# XFader_Assign.net
KiCad netlist of a schematic drawn in EAGLE
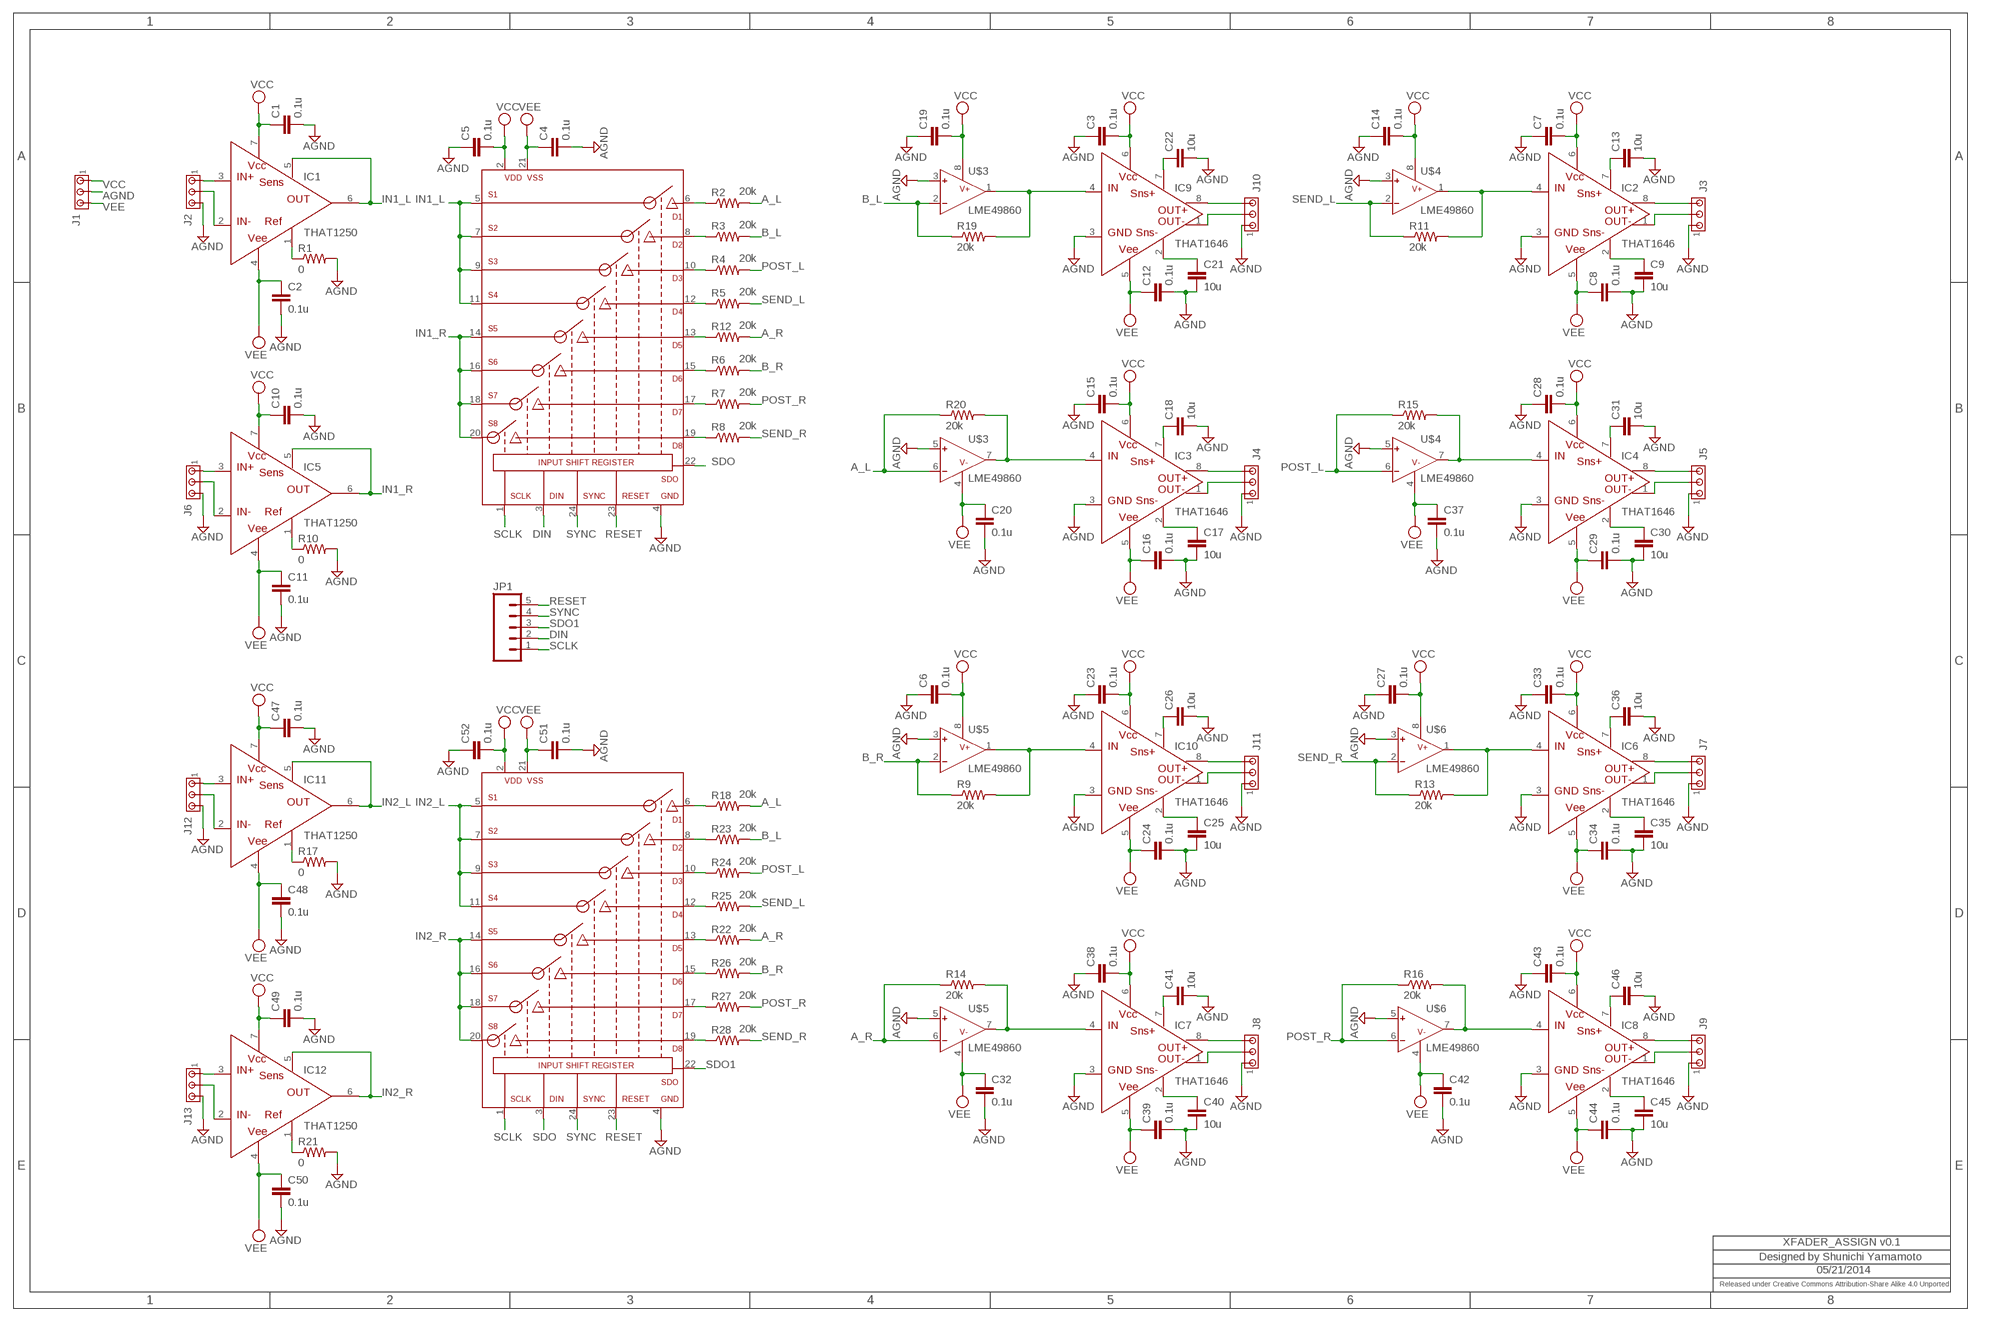
[diagram p0: schematic, sheet 1]

(export (version "E")
  (design (tool "Eeschema 10.0.6"))
  (components
    (comp (ref "C1")
      (value "0.1u")
      (footprint "eagle-import:C2012")
      (libsource (lib "eagle-import") (part "C-EUC2012"))
    )
    (comp (ref "C2")
      (value "0.1u")
      (footprint "eagle-import:C2012")
      (libsource (lib "eagle-import") (part "C-EUC2012"))
    )
    (comp (ref "C3")
      (value "0.1u")
      (footprint "eagle-import:C2012")
      (libsource (lib "eagle-import") (part "C-EUC2012"))
    )
    (comp (ref "C4")
      (value "0.1u")
      (footprint "eagle-import:C2012")
      (libsource (lib "eagle-import") (part "C-EUC2012"))
    )
    (comp (ref "C5")
      (value "0.1u")
      (footprint "eagle-import:C2012")
      (libsource (lib "eagle-import") (part "C-EUC2012"))
    )
    (comp (ref "C6")
      (value "0.1u")
      (footprint "eagle-import:C2012")
      (libsource (lib "eagle-import") (part "C-EUC2012"))
    )
    (comp (ref "C7")
      (value "0.1u")
      (footprint "eagle-import:C2012")
      (libsource (lib "eagle-import") (part "C-EUC2012"))
    )
    (comp (ref "C8")
      (value "0.1u")
      (footprint "eagle-import:C2012")
      (libsource (lib "eagle-import") (part "C-EUC2012"))
    )
    (comp (ref "C9")
      (value "10u")
      (footprint "eagle-import:C2012")
      (libsource (lib "eagle-import") (part "C-EUC2012"))
    )
    (comp (ref "C10")
      (value "0.1u")
      (footprint "eagle-import:C2012")
      (libsource (lib "eagle-import") (part "C-EUC2012"))
    )
    (comp (ref "C11")
      (value "0.1u")
      (footprint "eagle-import:C2012")
      (libsource (lib "eagle-import") (part "C-EUC2012"))
    )
    (comp (ref "C12")
      (value "0.1u")
      (footprint "eagle-import:C2012")
      (libsource (lib "eagle-import") (part "C-EUC2012"))
    )
    (comp (ref "C13")
      (value "10u")
      (footprint "eagle-import:C2012")
      (libsource (lib "eagle-import") (part "C-EUC2012"))
    )
    (comp (ref "C14")
      (value "0.1u")
      (footprint "eagle-import:C2012")
      (libsource (lib "eagle-import") (part "C-EUC2012"))
    )
    (comp (ref "C15")
      (value "0.1u")
      (footprint "eagle-import:C2012")
      (libsource (lib "eagle-import") (part "C-EUC2012"))
    )
    (comp (ref "C16")
      (value "0.1u")
      (footprint "eagle-import:C2012")
      (libsource (lib "eagle-import") (part "C-EUC2012"))
    )
    (comp (ref "C17")
      (value "10u")
      (footprint "eagle-import:C2012")
      (libsource (lib "eagle-import") (part "C-EUC2012"))
    )
    (comp (ref "C18")
      (value "10u")
      (footprint "eagle-import:C2012")
      (libsource (lib "eagle-import") (part "C-EUC2012"))
    )
    (comp (ref "C19")
      (value "0.1u")
      (footprint "eagle-import:C2012")
      (libsource (lib "eagle-import") (part "C-EUC2012"))
    )
    (comp (ref "C20")
      (value "0.1u")
      (footprint "eagle-import:C2012")
      (libsource (lib "eagle-import") (part "C-EUC2012"))
    )
    (comp (ref "C21")
      (value "10u")
      (footprint "eagle-import:C2012")
      (libsource (lib "eagle-import") (part "C-EUC2012"))
    )
    (comp (ref "C22")
      (value "10u")
      (footprint "eagle-import:C2012")
      (libsource (lib "eagle-import") (part "C-EUC2012"))
    )
    (comp (ref "C23")
      (value "0.1u")
      (footprint "eagle-import:C2012")
      (libsource (lib "eagle-import") (part "C-EUC2012"))
    )
    (comp (ref "C24")
      (value "0.1u")
      (footprint "eagle-import:C2012")
      (libsource (lib "eagle-import") (part "C-EUC2012"))
    )
    (comp (ref "C25")
      (value "10u")
      (footprint "eagle-import:C2012")
      (libsource (lib "eagle-import") (part "C-EUC2012"))
    )
    (comp (ref "C26")
      (value "10u")
      (footprint "eagle-import:C2012")
      (libsource (lib "eagle-import") (part "C-EUC2012"))
    )
    (comp (ref "C27")
      (value "0.1u")
      (footprint "eagle-import:C2012")
      (libsource (lib "eagle-import") (part "C-EUC2012"))
    )
    (comp (ref "C28")
      (value "0.1u")
      (footprint "eagle-import:C2012")
      (libsource (lib "eagle-import") (part "C-EUC2012"))
    )
    (comp (ref "C29")
      (value "0.1u")
      (footprint "eagle-import:C2012")
      (libsource (lib "eagle-import") (part "C-EUC2012"))
    )
    (comp (ref "C30")
      (value "10u")
      (footprint "eagle-import:C2012")
      (libsource (lib "eagle-import") (part "C-EUC2012"))
    )
    (comp (ref "C31")
      (value "10u")
      (footprint "eagle-import:C2012")
      (libsource (lib "eagle-import") (part "C-EUC2012"))
    )
    (comp (ref "C32")
      (value "0.1u")
      (footprint "eagle-import:C2012")
      (libsource (lib "eagle-import") (part "C-EUC2012"))
    )
    (comp (ref "C33")
      (value "0.1u")
      (footprint "eagle-import:C2012")
      (libsource (lib "eagle-import") (part "C-EUC2012"))
    )
    (comp (ref "C34")
      (value "0.1u")
      (footprint "eagle-import:C2012")
      (libsource (lib "eagle-import") (part "C-EUC2012"))
    )
    (comp (ref "C35")
      (value "10u")
      (footprint "eagle-import:C2012")
      (libsource (lib "eagle-import") (part "C-EUC2012"))
    )
    (comp (ref "C36")
      (value "10u")
      (footprint "eagle-import:C2012")
      (libsource (lib "eagle-import") (part "C-EUC2012"))
    )
    (comp (ref "C37")
      (value "0.1u")
      (footprint "eagle-import:C2012")
      (libsource (lib "eagle-import") (part "C-EUC2012"))
    )
    (comp (ref "C38")
      (value "0.1u")
      (footprint "eagle-import:C2012")
      (libsource (lib "eagle-import") (part "C-EUC2012"))
    )
    (comp (ref "C39")
      (value "0.1u")
      (footprint "eagle-import:C2012")
      (libsource (lib "eagle-import") (part "C-EUC2012"))
    )
    (comp (ref "C40")
      (value "10u")
      (footprint "eagle-import:C2012")
      (libsource (lib "eagle-import") (part "C-EUC2012"))
    )
    (comp (ref "C41")
      (value "10u")
      (footprint "eagle-import:C2012")
      (libsource (lib "eagle-import") (part "C-EUC2012"))
    )
    (comp (ref "C42")
      (value "0.1u")
      (footprint "eagle-import:C2012")
      (libsource (lib "eagle-import") (part "C-EUC2012"))
    )
    (comp (ref "C43")
      (value "0.1u")
      (footprint "eagle-import:C2012")
      (libsource (lib "eagle-import") (part "C-EUC2012"))
    )
    (comp (ref "C44")
      (value "0.1u")
      (footprint "eagle-import:C2012")
      (libsource (lib "eagle-import") (part "C-EUC2012"))
    )
    (comp (ref "C45")
      (value "10u")
      (footprint "eagle-import:C2012")
      (libsource (lib "eagle-import") (part "C-EUC2012"))
    )
    (comp (ref "C46")
      (value "10u")
      (footprint "eagle-import:C2012")
      (libsource (lib "eagle-import") (part "C-EUC2012"))
    )
    (comp (ref "C47")
      (value "0.1u")
      (footprint "eagle-import:C2012")
      (libsource (lib "eagle-import") (part "C-EUC2012"))
    )
    (comp (ref "C48")
      (value "0.1u")
      (footprint "eagle-import:C2012")
      (libsource (lib "eagle-import") (part "C-EUC2012"))
    )
    (comp (ref "C49")
      (value "0.1u")
      (footprint "eagle-import:C2012")
      (libsource (lib "eagle-import") (part "C-EUC2012"))
    )
    (comp (ref "C50")
      (value "0.1u")
      (footprint "eagle-import:C2012")
      (libsource (lib "eagle-import") (part "C-EUC2012"))
    )
    (comp (ref "C51")
      (value "0.1u")
      (footprint "eagle-import:C2012")
      (libsource (lib "eagle-import") (part "C-EUC2012"))
    )
    (comp (ref "C52")
      (value "0.1u")
      (footprint "eagle-import:C2012")
      (libsource (lib "eagle-import") (part "C-EUC2012"))
    )
    (comp (ref "IC1")
      (value "THAT1250")
      (footprint "eagle-import:SOIC8@1")
      (libsource (lib "eagle-import") (part "THAT1250"))
    )
    (comp (ref "IC2")
      (value "THAT1646")
      (footprint "eagle-import:SOIC8")
      (libsource (lib "eagle-import") (part "THAT1646"))
    )
    (comp (ref "IC3")
      (value "THAT1646")
      (footprint "eagle-import:SOIC8")
      (libsource (lib "eagle-import") (part "THAT1646"))
    )
    (comp (ref "IC4")
      (value "THAT1646")
      (footprint "eagle-import:SOIC8")
      (libsource (lib "eagle-import") (part "THAT1646"))
    )
    (comp (ref "IC5")
      (value "THAT1250")
      (footprint "eagle-import:SOIC8@1")
      (libsource (lib "eagle-import") (part "THAT1250"))
    )
    (comp (ref "IC6")
      (value "THAT1646")
      (footprint "eagle-import:SOIC8")
      (libsource (lib "eagle-import") (part "THAT1646"))
    )
    (comp (ref "IC7")
      (value "THAT1646")
      (footprint "eagle-import:SOIC8")
      (libsource (lib "eagle-import") (part "THAT1646"))
    )
    (comp (ref "IC8")
      (value "THAT1646")
      (footprint "eagle-import:SOIC8")
      (libsource (lib "eagle-import") (part "THAT1646"))
    )
    (comp (ref "IC9")
      (value "THAT1646")
      (footprint "eagle-import:SOIC8")
      (libsource (lib "eagle-import") (part "THAT1646"))
    )
    (comp (ref "IC10")
      (value "THAT1646")
      (footprint "eagle-import:SOIC8")
      (libsource (lib "eagle-import") (part "THAT1646"))
    )
    (comp (ref "IC11")
      (value "THAT1250")
      (footprint "eagle-import:SOIC8@1")
      (libsource (lib "eagle-import") (part "THAT1250"))
    )
    (comp (ref "IC12")
      (value "THAT1250")
      (footprint "eagle-import:SOIC8@1")
      (libsource (lib "eagle-import") (part "THAT1250"))
    )
    (comp (ref "J1")
      (value "MTA03-156")
      (footprint "eagle-import:1X3MTA")
      (libsource (lib "eagle-import") (part "MTA03-156"))
    )
    (comp (ref "J2")
      (value "MTA03-100")
      (footprint "eagle-import:10X03MTA")
      (libsource (lib "eagle-import") (part "MTA03-100"))
    )
    (comp (ref "J3")
      (value "MTA03-100")
      (footprint "eagle-import:10X03MTA")
      (libsource (lib "eagle-import") (part "MTA03-100"))
    )
    (comp (ref "J4")
      (value "MTA03-100")
      (footprint "eagle-import:10X03MTA")
      (libsource (lib "eagle-import") (part "MTA03-100"))
    )
    (comp (ref "J5")
      (value "MTA03-100")
      (footprint "eagle-import:10X03MTA")
      (libsource (lib "eagle-import") (part "MTA03-100"))
    )
    (comp (ref "J6")
      (value "MTA03-100")
      (footprint "eagle-import:10X03MTA")
      (libsource (lib "eagle-import") (part "MTA03-100"))
    )
    (comp (ref "J7")
      (value "MTA03-100")
      (footprint "eagle-import:10X03MTA")
      (libsource (lib "eagle-import") (part "MTA03-100"))
    )
    (comp (ref "J8")
      (value "MTA03-100")
      (footprint "eagle-import:10X03MTA")
      (libsource (lib "eagle-import") (part "MTA03-100"))
    )
    (comp (ref "J9")
      (value "MTA03-100")
      (footprint "eagle-import:10X03MTA")
      (libsource (lib "eagle-import") (part "MTA03-100"))
    )
    (comp (ref "J10")
      (value "MTA03-100")
      (footprint "eagle-import:10X03MTA")
      (libsource (lib "eagle-import") (part "MTA03-100"))
    )
    (comp (ref "J11")
      (value "MTA03-100")
      (footprint "eagle-import:10X03MTA")
      (libsource (lib "eagle-import") (part "MTA03-100"))
    )
    (comp (ref "J12")
      (value "MTA03-100")
      (footprint "eagle-import:10X03MTA")
      (libsource (lib "eagle-import") (part "MTA03-100"))
    )
    (comp (ref "J13")
      (value "MTA03-100")
      (footprint "eagle-import:10X03MTA")
      (libsource (lib "eagle-import") (part "MTA03-100"))
    )
    (comp (ref "JP1")
      (value "M05PTH")
      (footprint "eagle-import:1X05")
      (libsource (lib "eagle-import") (part "M05PTH"))
    )
    (comp (ref "R1")
      (value "0")
      (footprint "eagle-import:0805")
      (libsource (lib "eagle-import") (part "RESISTOR0805-RES"))
    )
    (comp (ref "R2")
      (value "20k")
      (footprint "eagle-import:0805")
      (libsource (lib "eagle-import") (part "RESISTOR0805-RES"))
    )
    (comp (ref "R3")
      (value "20k")
      (footprint "eagle-import:0805")
      (libsource (lib "eagle-import") (part "RESISTOR0805-RES"))
    )
    (comp (ref "R4")
      (value "20k")
      (footprint "eagle-import:0805")
      (libsource (lib "eagle-import") (part "RESISTOR0805-RES"))
    )
    (comp (ref "R5")
      (value "20k")
      (footprint "eagle-import:0805")
      (libsource (lib "eagle-import") (part "RESISTOR0805-RES"))
    )
    (comp (ref "R6")
      (value "20k")
      (footprint "eagle-import:0805")
      (libsource (lib "eagle-import") (part "RESISTOR0805-RES"))
    )
    (comp (ref "R7")
      (value "20k")
      (footprint "eagle-import:0805")
      (libsource (lib "eagle-import") (part "RESISTOR0805-RES"))
    )
    (comp (ref "R8")
      (value "20k")
      (footprint "eagle-import:0805")
      (libsource (lib "eagle-import") (part "RESISTOR0805-RES"))
    )
    (comp (ref "R9")
      (value "20k")
      (footprint "eagle-import:0805")
      (libsource (lib "eagle-import") (part "RESISTOR0805-RES"))
    )
    (comp (ref "R10")
      (value "0")
      (footprint "eagle-import:0805")
      (libsource (lib "eagle-import") (part "RESISTOR0805-RES"))
    )
    (comp (ref "R11")
      (value "20k")
      (footprint "eagle-import:0805")
      (libsource (lib "eagle-import") (part "RESISTOR0805-RES"))
    )
    (comp (ref "R12")
      (value "20k")
      (footprint "eagle-import:0805")
      (libsource (lib "eagle-import") (part "RESISTOR0805-RES"))
    )
    (comp (ref "R13")
      (value "20k")
      (footprint "eagle-import:0805")
      (libsource (lib "eagle-import") (part "RESISTOR0805-RES"))
    )
    (comp (ref "R14")
      (value "20k")
      (footprint "eagle-import:0805")
      (libsource (lib "eagle-import") (part "RESISTOR0805-RES"))
    )
    (comp (ref "R15")
      (value "20k")
      (footprint "eagle-import:0805")
      (libsource (lib "eagle-import") (part "RESISTOR0805-RES"))
    )
    (comp (ref "R16")
      (value "20k")
      (footprint "eagle-import:0805")
      (libsource (lib "eagle-import") (part "RESISTOR0805-RES"))
    )
    (comp (ref "R17")
      (value "0")
      (footprint "eagle-import:0805")
      (libsource (lib "eagle-import") (part "RESISTOR0805-RES"))
    )
    (comp (ref "R18")
      (value "20k")
      (footprint "eagle-import:0805")
      (libsource (lib "eagle-import") (part "RESISTOR0805-RES"))
    )
    (comp (ref "R19")
      (value "20k")
      (footprint "eagle-import:0805")
      (libsource (lib "eagle-import") (part "RESISTOR0805-RES"))
    )
    (comp (ref "R20")
      (value "20k")
      (footprint "eagle-import:0805")
      (libsource (lib "eagle-import") (part "RESISTOR0805-RES"))
    )
    (comp (ref "R21")
      (value "0")
      (footprint "eagle-import:0805")
      (libsource (lib "eagle-import") (part "RESISTOR0805-RES"))
    )
    (comp (ref "R22")
      (value "20k")
      (footprint "eagle-import:0805")
      (libsource (lib "eagle-import") (part "RESISTOR0805-RES"))
    )
    (comp (ref "R23")
      (value "20k")
      (footprint "eagle-import:0805")
      (libsource (lib "eagle-import") (part "RESISTOR0805-RES"))
    )
    (comp (ref "R24")
      (value "20k")
      (footprint "eagle-import:0805")
      (libsource (lib "eagle-import") (part "RESISTOR0805-RES"))
    )
    (comp (ref "R25")
      (value "20k")
      (footprint "eagle-import:0805")
      (libsource (lib "eagle-import") (part "RESISTOR0805-RES"))
    )
    (comp (ref "R26")
      (value "20k")
      (footprint "eagle-import:0805")
      (libsource (lib "eagle-import") (part "RESISTOR0805-RES"))
    )
    (comp (ref "R27")
      (value "20k")
      (footprint "eagle-import:0805")
      (libsource (lib "eagle-import") (part "RESISTOR0805-RES"))
    )
    (comp (ref "R28")
      (value "20k")
      (footprint "eagle-import:0805")
      (libsource (lib "eagle-import") (part "RESISTOR0805-RES"))
    )
    (comp (ref "U$1")
      (value "ADG1414")
      (footprint "eagle-import:TSSOP24")
      (libsource (lib "eagle-import") (part "ADG1414"))
    )
    (comp (ref "U$2")
      (value "ADG1414")
      (footprint "eagle-import:TSSOP24")
      (libsource (lib "eagle-import") (part "ADG1414"))
    )
    (comp (ref "U$3")
      (value "LME49860")
      (footprint "eagle-import:SOIC8")
      (libsource (lib "eagle-import") (part "LME49860"))
    )
    (comp (ref "U$4")
      (value "LME49860")
      (footprint "eagle-import:SOIC8")
      (libsource (lib "eagle-import") (part "LME49860"))
    )
    (comp (ref "U$5")
      (value "LME49860")
      (footprint "eagle-import:SOIC8")
      (libsource (lib "eagle-import") (part "LME49860"))
    )
    (comp (ref "U$6")
      (value "LME49860")
      (footprint "eagle-import:SOIC8")
      (libsource (lib "eagle-import") (part "LME49860"))
    )
  )
  (nets
    (net (code "1") (name "/A_L") (class "Default")
      (node (ref "R18") (pin "2") (pinfunction "2_2") (pintype "passive"))
      (node (ref "R2") (pin "2") (pinfunction "2_2") (pintype "passive"))
      (node (ref "R20") (pin "1") (pinfunction "1_1") (pintype "passive"))
      (node (ref "U$3") (pin "6") (pinfunction "INB-_6") (pintype "input"))
    )
    (net (code "2") (name "/A_R") (class "Default")
      (node (ref "R12") (pin "2") (pinfunction "2_2") (pintype "passive"))
      (node (ref "R14") (pin "1") (pinfunction "1_1") (pintype "passive"))
      (node (ref "R22") (pin "2") (pinfunction "2_2") (pintype "passive"))
      (node (ref "U$5") (pin "6") (pinfunction "INB-_6") (pintype "input"))
    )
    (net (code "3") (name "/B_L") (class "Default")
      (node (ref "R19") (pin "1") (pinfunction "1_1") (pintype "passive"))
      (node (ref "R23") (pin "2") (pinfunction "2_2") (pintype "passive"))
      (node (ref "R3") (pin "2") (pinfunction "2_2") (pintype "passive"))
      (node (ref "U$3") (pin "2") (pinfunction "INA-_2") (pintype "input"))
    )
    (net (code "4") (name "/B_R") (class "Default")
      (node (ref "R26") (pin "2") (pinfunction "2_2") (pintype "passive"))
      (node (ref "R6") (pin "2") (pinfunction "2_2") (pintype "passive"))
      (node (ref "R9") (pin "1") (pinfunction "1_1") (pintype "passive"))
      (node (ref "U$5") (pin "2") (pinfunction "INA-_2") (pintype "input"))
    )
    (net (code "5") (name "/DIN") (class "Default")
      (node (ref "JP1") (pin "2") (pinfunction "2_2") (pintype "passive"))
      (node (ref "U$1") (pin "3") (pinfunction "DIN_3") (pintype "input"))
    )
    (net (code "6") (name "/IN1_L") (class "Default")
      (node (ref "IC1") (pin "5") (pinfunction "SENS_5") (pintype "power_in"))
      (node (ref "IC1") (pin "6") (pinfunction "OUT_6") (pintype "output"))
      (node (ref "U$1") (pin "11") (pinfunction "S4_11") (pintype "input"))
      (node (ref "U$1") (pin "5") (pinfunction "S1_5") (pintype "input"))
      (node (ref "U$1") (pin "7") (pinfunction "S2_7") (pintype "input"))
      (node (ref "U$1") (pin "9") (pinfunction "S3_9") (pintype "input"))
    )
    (net (code "7") (name "/IN1_R") (class "Default")
      (node (ref "IC5") (pin "5") (pinfunction "SENS_5") (pintype "power_in"))
      (node (ref "IC5") (pin "6") (pinfunction "OUT_6") (pintype "output"))
      (node (ref "U$1") (pin "14") (pinfunction "S5_14") (pintype "input"))
      (node (ref "U$1") (pin "16") (pinfunction "S6_16") (pintype "input"))
      (node (ref "U$1") (pin "18") (pinfunction "S7_18") (pintype "input"))
      (node (ref "U$1") (pin "20") (pinfunction "S8_20") (pintype "input"))
    )
    (net (code "8") (name "/IN2_L") (class "Default")
      (node (ref "IC11") (pin "5") (pinfunction "SENS_5") (pintype "power_in"))
      (node (ref "IC11") (pin "6") (pinfunction "OUT_6") (pintype "output"))
      (node (ref "U$2") (pin "11") (pinfunction "S4_11") (pintype "input"))
      (node (ref "U$2") (pin "5") (pinfunction "S1_5") (pintype "input"))
      (node (ref "U$2") (pin "7") (pinfunction "S2_7") (pintype "input"))
      (node (ref "U$2") (pin "9") (pinfunction "S3_9") (pintype "input"))
    )
    (net (code "9") (name "/IN2_R") (class "Default")
      (node (ref "IC12") (pin "5") (pinfunction "SENS_5") (pintype "power_in"))
      (node (ref "IC12") (pin "6") (pinfunction "OUT_6") (pintype "output"))
      (node (ref "U$2") (pin "14") (pinfunction "S5_14") (pintype "input"))
      (node (ref "U$2") (pin "16") (pinfunction "S6_16") (pintype "input"))
      (node (ref "U$2") (pin "18") (pinfunction "S7_18") (pintype "input"))
      (node (ref "U$2") (pin "20") (pinfunction "S8_20") (pintype "input"))
    )
    (net (code "10") (name "/POST_L") (class "Default")
      (node (ref "R15") (pin "1") (pinfunction "1_1") (pintype "passive"))
      (node (ref "R24") (pin "2") (pinfunction "2_2") (pintype "passive"))
      (node (ref "R4") (pin "2") (pinfunction "2_2") (pintype "passive"))
      (node (ref "U$4") (pin "6") (pinfunction "INB-_6") (pintype "input"))
    )
    (net (code "11") (name "/POST_R") (class "Default")
      (node (ref "R16") (pin "1") (pinfunction "1_1") (pintype "passive"))
      (node (ref "R27") (pin "2") (pinfunction "2_2") (pintype "passive"))
      (node (ref "R7") (pin "2") (pinfunction "2_2") (pintype "passive"))
      (node (ref "U$6") (pin "6") (pinfunction "INB-_6") (pintype "input"))
    )
    (net (code "12") (name "/RESET") (class "Default")
      (node (ref "JP1") (pin "5") (pinfunction "5_5") (pintype "passive"))
      (node (ref "U$1") (pin "23") (pinfunction "RESET_23") (pintype "input"))
      (node (ref "U$2") (pin "23") (pinfunction "RESET_23") (pintype "input"))
    )
    (net (code "13") (name "/SCLK") (class "Default")
      (node (ref "JP1") (pin "1") (pinfunction "1_1") (pintype "passive"))
      (node (ref "U$1") (pin "1") (pinfunction "SCLK_1") (pintype "input"))
      (node (ref "U$2") (pin "1") (pinfunction "SCLK_1") (pintype "input"))
    )
    (net (code "14") (name "/SDO") (class "Default")
      (node (ref "U$1") (pin "22") (pinfunction "SDO_22") (pintype "output"))
      (node (ref "U$2") (pin "3") (pinfunction "DIN_3") (pintype "input"))
    )
    (net (code "15") (name "/SDO1") (class "Default")
      (node (ref "JP1") (pin "3") (pinfunction "3_3") (pintype "passive"))
      (node (ref "U$2") (pin "22") (pinfunction "SDO_22") (pintype "output"))
    )
    (net (code "16") (name "/SEND_L") (class "Default")
      (node (ref "R11") (pin "1") (pinfunction "1_1") (pintype "passive"))
      (node (ref "R25") (pin "2") (pinfunction "2_2") (pintype "passive"))
      (node (ref "R5") (pin "2") (pinfunction "2_2") (pintype "passive"))
      (node (ref "U$4") (pin "2") (pinfunction "INA-_2") (pintype "input"))
    )
    (net (code "17") (name "/SEND_R") (class "Default")
      (node (ref "R13") (pin "1") (pinfunction "1_1") (pintype "passive"))
      (node (ref "R28") (pin "2") (pinfunction "2_2") (pintype "passive"))
      (node (ref "R8") (pin "2") (pinfunction "2_2") (pintype "passive"))
      (node (ref "U$6") (pin "2") (pinfunction "INA-_2") (pintype "input"))
    )
    (net (code "18") (name "/SYNC") (class "Default")
      (node (ref "JP1") (pin "4") (pinfunction "4_4") (pintype "passive"))
      (node (ref "U$1") (pin "24") (pinfunction "SYNC_24") (pintype "input"))
      (node (ref "U$2") (pin "24") (pinfunction "SYNC_24") (pintype "input"))
    )
    (net (code "19") (name "AGND") (class "Default")
      (node (ref "C1") (pin "2") (pinfunction "2_2") (pintype "passive"))
      (node (ref "C10") (pin "2") (pinfunction "2_2") (pintype "passive"))
      (node (ref "C11") (pin "2") (pinfunction "2_2") (pintype "passive"))
      (node (ref "C12") (pin "2") (pinfunction "2_2") (pintype "passive"))
      (node (ref "C13") (pin "2") (pinfunction "2_2") (pintype "passive"))
      (node (ref "C14") (pin "1") (pinfunction "1_1") (pintype "passive"))
      (node (ref "C15") (pin "1") (pinfunction "1_1") (pintype "passive"))
      (node (ref "C16") (pin "2") (pinfunction "2_2") (pintype "passive"))
      (node (ref "C17") (pin "2") (pinfunction "2_2") (pintype "passive"))
      (node (ref "C18") (pin "2") (pinfunction "2_2") (pintype "passive"))
      (node (ref "C19") (pin "1") (pinfunction "1_1") (pintype "passive"))
      (node (ref "C2") (pin "2") (pinfunction "2_2") (pintype "passive"))
      (node (ref "C20") (pin "2") (pinfunction "2_2") (pintype "passive"))
      (node (ref "C21") (pin "2") (pinfunction "2_2") (pintype "passive"))
      (node (ref "C22") (pin "2") (pinfunction "2_2") (pintype "passive"))
      (node (ref "C23") (pin "1") (pinfunction "1_1") (pintype "passive"))
      (node (ref "C24") (pin "2") (pinfunction "2_2") (pintype "passive"))
      (node (ref "C25") (pin "2") (pinfunction "2_2") (pintype "passive"))
      (node (ref "C26") (pin "2") (pinfunction "2_2") (pintype "passive"))
      (node (ref "C27") (pin "1") (pinfunction "1_1") (pintype "passive"))
      (node (ref "C28") (pin "1") (pinfunction "1_1") (pintype "passive"))
      (node (ref "C29") (pin "2") (pinfunction "2_2") (pintype "passive"))
      (node (ref "C3") (pin "1") (pinfunction "1_1") (pintype "passive"))
      (node (ref "C30") (pin "2") (pinfunction "2_2") (pintype "passive"))
      (node (ref "C31") (pin "2") (pinfunction "2_2") (pintype "passive"))
      (node (ref "C32") (pin "2") (pinfunction "2_2") (pintype "passive"))
      (node (ref "C33") (pin "1") (pinfunction "1_1") (pintype "passive"))
      (node (ref "C34") (pin "2") (pinfunction "2_2") (pintype "passive"))
      (node (ref "C35") (pin "2") (pinfunction "2_2") (pintype "passive"))
      (node (ref "C36") (pin "2") (pinfunction "2_2") (pintype "passive"))
      (node (ref "C37") (pin "2") (pinfunction "2_2") (pintype "passive"))
      (node (ref "C38") (pin "1") (pinfunction "1_1") (pintype "passive"))
      (node (ref "C39") (pin "2") (pinfunction "2_2") (pintype "passive"))
      (node (ref "C4") (pin "2") (pinfunction "2_2") (pintype "passive"))
      (node (ref "C40") (pin "2") (pinfunction "2_2") (pintype "passive"))
      (node (ref "C41") (pin "2") (pinfunction "2_2") (pintype "passive"))
      (node (ref "C42") (pin "2") (pinfunction "2_2") (pintype "passive"))
      (node (ref "C43") (pin "1") (pinfunction "1_1") (pintype "passive"))
      (node (ref "C44") (pin "2") (pinfunction "2_2") (pintype "passive"))
      (node (ref "C45") (pin "2") (pinfunction "2_2") (pintype "passive"))
      (node (ref "C46") (pin "2") (pinfunction "2_2") (pintype "passive"))
      (node (ref "C47") (pin "2") (pinfunction "2_2") (pintype "passive"))
      (node (ref "C48") (pin "2") (pinfunction "2_2") (pintype "passive"))
      (node (ref "C49") (pin "2") (pinfunction "2_2") (pintype "passive"))
      (node (ref "C5") (pin "1") (pinfunction "1_1") (pintype "passive"))
      (node (ref "C50") (pin "2") (pinfunction "2_2") (pintype "passive"))
      (node (ref "C51") (pin "2") (pinfunction "2_2") (pintype "passive"))
      (node (ref "C52") (pin "1") (pinfunction "1_1") (pintype "passive"))
      (node (ref "C6") (pin "1") (pinfunction "1_1") (pintype "passive"))
      (node (ref "C7") (pin "1") (pinfunction "1_1") (pintype "passive"))
      (node (ref "C8") (pin "2") (pinfunction "2_2") (pintype "passive"))
      (node (ref "C9") (pin "2") (pinfunction "2_2") (pintype "passive"))
      (node (ref "IC10") (pin "3") (pinfunction "GND_3") (pintype "input"))
      (node (ref "IC2") (pin "3") (pinfunction "GND_3") (pintype "input"))
      (node (ref "IC3") (pin "3") (pinfunction "GND_3") (pintype "input"))
      (node (ref "IC4") (pin "3") (pinfunction "GND_3") (pintype "input"))
      (node (ref "IC6") (pin "3") (pinfunction "GND_3") (pintype "input"))
      (node (ref "IC7") (pin "3") (pinfunction "GND_3") (pintype "input"))
      (node (ref "IC8") (pin "3") (pinfunction "GND_3") (pintype "input"))
      (node (ref "IC9") (pin "3") (pinfunction "GND_3") (pintype "input"))
      (node (ref "J1") (pin "2") (pinfunction "2_2") (pintype "passive"))
      (node (ref "J10") (pin "1") (pinfunction "1_1") (pintype "passive"))
      (node (ref "J11") (pin "1") (pinfunction "1_1") (pintype "passive"))
      (node (ref "J12") (pin "3") (pinfunction "3_3") (pintype "passive"))
      (node (ref "J13") (pin "3") (pinfunction "3_3") (pintype "passive"))
      (node (ref "J2") (pin "3") (pinfunction "3_3") (pintype "passive"))
      (node (ref "J3") (pin "1") (pinfunction "1_1") (pintype "passive"))
      (node (ref "J4") (pin "1") (pinfunction "1_1") (pintype "passive"))
      (node (ref "J5") (pin "1") (pinfunction "1_1") (pintype "passive"))
      (node (ref "J6") (pin "3") (pinfunction "3_3") (pintype "passive"))
      (node (ref "J7") (pin "1") (pinfunction "1_1") (pintype "passive"))
      (node (ref "J8") (pin "1") (pinfunction "1_1") (pintype "passive"))
      (node (ref "J9") (pin "1") (pinfunction "1_1") (pintype "passive"))
      (node (ref "R1") (pin "2") (pinfunction "2_2") (pintype "passive"))
      (node (ref "R10") (pin "2") (pinfunction "2_2") (pintype "passive"))
      (node (ref "R17") (pin "2") (pinfunction "2_2") (pintype "passive"))
      (node (ref "R21") (pin "2") (pinfunction "2_2") (pintype "passive"))
      (node (ref "U$1") (pin "4") (pinfunction "GND_4") (pintype "power_in"))
      (node (ref "U$2") (pin "4") (pinfunction "GND_4") (pintype "power_in"))
      (node (ref "U$3") (pin "3") (pinfunction "INA+_3") (pintype "input"))
      (node (ref "U$3") (pin "5") (pinfunction "INB+_5") (pintype "input"))
      (node (ref "U$4") (pin "3") (pinfunction "INA+_3") (pintype "input"))
      (node (ref "U$4") (pin "5") (pinfunction "INB+_5") (pintype "input"))
      (node (ref "U$5") (pin "3") (pinfunction "INA+_3") (pintype "input"))
      (node (ref "U$5") (pin "5") (pinfunction "INB+_5") (pintype "input"))
      (node (ref "U$6") (pin "3") (pinfunction "INA+_3") (pintype "input"))
      (node (ref "U$6") (pin "5") (pinfunction "INB+_5") (pintype "input"))
    )
    (net (code "20") (name "Net-(IC1-IN+)") (class "Default")
      (node (ref "IC1") (pin "3") (pinfunction "IN+_3") (pintype "input"))
      (node (ref "J2") (pin "1") (pinfunction "1_1") (pintype "passive"))
    )
    (net (code "21") (name "Net-(IC1-IN-)") (class "Default")
      (node (ref "IC1") (pin "2") (pinfunction "IN-_2") (pintype "input"))
      (node (ref "J2") (pin "2") (pinfunction "2_2") (pintype "passive"))
    )
    (net (code "22") (name "Net-(IC1-REF)") (class "Default")
      (node (ref "IC1") (pin "1") (pinfunction "REF_1") (pintype "input"))
      (node (ref "R1") (pin "1") (pinfunction "1_1") (pintype "passive"))
    )
    (net (code "23") (name "Net-(IC2-IN)") (class "Default")
      (node (ref "IC2") (pin "4") (pinfunction "IN_4") (pintype "input"))
      (node (ref "R11") (pin "2") (pinfunction "2_2") (pintype "passive"))
      (node (ref "U$4") (pin "1") (pinfunction "OUTA_1") (pintype "output"))
    )
    (net (code "24") (name "Net-(IC2-OUT+)") (class "Default")
      (node (ref "IC2") (pin "8") (pinfunction "OUT+_8") (pintype "output"))
      (node (ref "J3") (pin "3") (pinfunction "3_3") (pintype "passive"))
    )
    (net (code "25") (name "Net-(IC2-OUT-)") (class "Default")
      (node (ref "IC2") (pin "1") (pinfunction "OUT-_1") (pintype "output"))
      (node (ref "J3") (pin "2") (pinfunction "2_2") (pintype "passive"))
    )
    (net (code "26") (name "Net-(IC2-SNS+)") (class "Default")
      (node (ref "C13") (pin "1") (pinfunction "1_1") (pintype "passive"))
      (node (ref "IC2") (pin "7") (pinfunction "SNS+_7") (pintype "power_in"))
    )
    (net (code "27") (name "Net-(IC2-SNS-)") (class "Default")
      (node (ref "C9") (pin "1") (pinfunction "1_1") (pintype "passive"))
      (node (ref "IC2") (pin "2") (pinfunction "SNS-_2") (pintype "input"))
    )
    (net (code "28") (name "Net-(IC3-IN)") (class "Default")
      (node (ref "IC3") (pin "4") (pinfunction "IN_4") (pintype "input"))
      (node (ref "R20") (pin "2") (pinfunction "2_2") (pintype "passive"))
      (node (ref "U$3") (pin "7") (pinfunction "OUTB_7") (pintype "output"))
    )
    (net (code "29") (name "Net-(IC3-OUT+)") (class "Default")
      (node (ref "IC3") (pin "8") (pinfunction "OUT+_8") (pintype "output"))
      (node (ref "J4") (pin "3") (pinfunction "3_3") (pintype "passive"))
    )
    (net (code "30") (name "Net-(IC3-OUT-)") (class "Default")
      (node (ref "IC3") (pin "1") (pinfunction "OUT-_1") (pintype "output"))
      (node (ref "J4") (pin "2") (pinfunction "2_2") (pintype "passive"))
    )
    (net (code "31") (name "Net-(IC3-SNS+)") (class "Default")
      (node (ref "C18") (pin "1") (pinfunction "1_1") (pintype "passive"))
      (node (ref "IC3") (pin "7") (pinfunction "SNS+_7") (pintype "power_in"))
    )
    (net (code "32") (name "Net-(IC3-SNS-)") (class "Default")
      (node (ref "C17") (pin "1") (pinfunction "1_1") (pintype "passive"))
      (node (ref "IC3") (pin "2") (pinfunction "SNS-_2") (pintype "input"))
    )
    (net (code "33") (name "Net-(IC4-IN)") (class "Default")
      (node (ref "IC4") (pin "4") (pinfunction "IN_4") (pintype "input"))
      (node (ref "R15") (pin "2") (pinfunction "2_2") (pintype "passive"))
      (node (ref "U$4") (pin "7") (pinfunction "OUTB_7") (pintype "output"))
    )
    (net (code "34") (name "Net-(IC4-OUT+)") (class "Default")
      (node (ref "IC4") (pin "8") (pinfunction "OUT+_8") (pintype "output"))
      (node (ref "J5") (pin "3") (pinfunction "3_3") (pintype "passive"))
    )
    (net (code "35") (name "Net-(IC4-OUT-)") (class "Default")
      (node (ref "IC4") (pin "1") (pinfunction "OUT-_1") (pintype "output"))
      (node (ref "J5") (pin "2") (pinfunction "2_2") (pintype "passive"))
    )
    (net (code "36") (name "Net-(IC4-SNS+)") (class "Default")
      (node (ref "C31") (pin "1") (pinfunction "1_1") (pintype "passive"))
      (node (ref "IC4") (pin "7") (pinfunction "SNS+_7") (pintype "power_in"))
    )
    (net (code "37") (name "Net-(IC4-SNS-)") (class "Default")
      (node (ref "C30") (pin "1") (pinfunction "1_1") (pintype "passive"))
      (node (ref "IC4") (pin "2") (pinfunction "SNS-_2") (pintype "input"))
    )
    (net (code "38") (name "Net-(IC5-IN+)") (class "Default")
      (node (ref "IC5") (pin "3") (pinfunction "IN+_3") (pintype "input"))
      (node (ref "J6") (pin "1") (pinfunction "1_1") (pintype "passive"))
    )
    (net (code "39") (name "Net-(IC5-IN-)") (class "Default")
      (node (ref "IC5") (pin "2") (pinfunction "IN-_2") (pintype "input"))
      (node (ref "J6") (pin "2") (pinfunction "2_2") (pintype "passive"))
    )
    (net (code "40") (name "Net-(IC5-REF)") (class "Default")
      (node (ref "IC5") (pin "1") (pinfunction "REF_1") (pintype "input"))
      (node (ref "R10") (pin "1") (pinfunction "1_1") (pintype "passive"))
    )
    (net (code "41") (name "Net-(IC6-IN)") (class "Default")
      (node (ref "IC6") (pin "4") (pinfunction "IN_4") (pintype "input"))
      (node (ref "R13") (pin "2") (pinfunction "2_2") (pintype "passive"))
      (node (ref "U$6") (pin "1") (pinfunction "OUTA_1") (pintype "output"))
    )
    (net (code "42") (name "Net-(IC6-OUT+)") (class "Default")
      (node (ref "IC6") (pin "8") (pinfunction "OUT+_8") (pintype "output"))
      (node (ref "J7") (pin "3") (pinfunction "3_3") (pintype "passive"))
    )
    (net (code "43") (name "Net-(IC6-OUT-)") (class "Default")
      (node (ref "IC6") (pin "1") (pinfunction "OUT-_1") (pintype "output"))
      (node (ref "J7") (pin "2") (pinfunction "2_2") (pintype "passive"))
    )
    (net (code "44") (name "Net-(IC6-SNS+)") (class "Default")
      (node (ref "C36") (pin "1") (pinfunction "1_1") (pintype "passive"))
      (node (ref "IC6") (pin "7") (pinfunction "SNS+_7") (pintype "power_in"))
    )
    (net (code "45") (name "Net-(IC6-SNS-)") (class "Default")
      (node (ref "C35") (pin "1") (pinfunction "1_1") (pintype "passive"))
      (node (ref "IC6") (pin "2") (pinfunction "SNS-_2") (pintype "input"))
    )
    (net (code "46") (name "Net-(IC7-IN)") (class "Default")
      (node (ref "IC7") (pin "4") (pinfunction "IN_4") (pintype "input"))
      (node (ref "R14") (pin "2") (pinfunction "2_2") (pintype "passive"))
      (node (ref "U$5") (pin "7") (pinfunction "OUTB_7") (pintype "output"))
    )
    (net (code "47") (name "Net-(IC7-OUT+)") (class "Default")
      (node (ref "IC7") (pin "8") (pinfunction "OUT+_8") (pintype "output"))
      (node (ref "J8") (pin "3") (pinfunction "3_3") (pintype "passive"))
    )
    (net (code "48") (name "Net-(IC7-OUT-)") (class "Default")
      (node (ref "IC7") (pin "1") (pinfunction "OUT-_1") (pintype "output"))
      (node (ref "J8") (pin "2") (pinfunction "2_2") (pintype "passive"))
    )
    (net (code "49") (name "Net-(IC7-SNS+)") (class "Default")
      (node (ref "C41") (pin "1") (pinfunction "1_1") (pintype "passive"))
      (node (ref "IC7") (pin "7") (pinfunction "SNS+_7") (pintype "power_in"))
    )
    (net (code "50") (name "Net-(IC7-SNS-)") (class "Default")
      (node (ref "C40") (pin "1") (pinfunction "1_1") (pintype "passive"))
      (node (ref "IC7") (pin "2") (pinfunction "SNS-_2") (pintype "input"))
    )
    (net (code "51") (name "Net-(IC8-IN)") (class "Default")
      (node (ref "IC8") (pin "4") (pinfunction "IN_4") (pintype "input"))
      (node (ref "R16") (pin "2") (pinfunction "2_2") (pintype "passive"))
      (node (ref "U$6") (pin "7") (pinfunction "OUTB_7") (pintype "output"))
    )
    (net (code "52") (name "Net-(IC8-OUT+)") (class "Default")
      (node (ref "IC8") (pin "8") (pinfunction "OUT+_8") (pintype "output"))
      (node (ref "J9") (pin "3") (pinfunction "3_3") (pintype "passive"))
    )
    (net (code "53") (name "Net-(IC8-OUT-)") (class "Default")
      (node (ref "IC8") (pin "1") (pinfunction "OUT-_1") (pintype "output"))
      (node (ref "J9") (pin "2") (pinfunction "2_2") (pintype "passive"))
    )
    (net (code "54") (name "Net-(IC8-SNS+)") (class "Default")
      (node (ref "C46") (pin "1") (pinfunction "1_1") (pintype "passive"))
      (node (ref "IC8") (pin "7") (pinfunction "SNS+_7") (pintype "power_in"))
    )
    (net (code "55") (name "Net-(IC8-SNS-)") (class "Default")
      (node (ref "C45") (pin "1") (pinfunction "1_1") (pintype "passive"))
      (node (ref "IC8") (pin "2") (pinfunction "SNS-_2") (pintype "input"))
    )
    (net (code "56") (name "Net-(IC9-IN)") (class "Default")
      (node (ref "IC9") (pin "4") (pinfunction "IN_4") (pintype "input"))
      (node (ref "R19") (pin "2") (pinfunction "2_2") (pintype "passive"))
      (node (ref "U$3") (pin "1") (pinfunction "OUTA_1") (pintype "output"))
    )
    (net (code "57") (name "Net-(IC9-OUT+)") (class "Default")
      (node (ref "IC9") (pin "8") (pinfunction "OUT+_8") (pintype "output"))
      (node (ref "J10") (pin "3") (pinfunction "3_3") (pintype "passive"))
    )
    (net (code "58") (name "Net-(IC9-OUT-)") (class "Default")
      (node (ref "IC9") (pin "1") (pinfunction "OUT-_1") (pintype "output"))
      (node (ref "J10") (pin "2") (pinfunction "2_2") (pintype "passive"))
    )
    (net (code "59") (name "Net-(IC9-SNS+)") (class "Default")
      (node (ref "C22") (pin "1") (pinfunction "1_1") (pintype "passive"))
      (node (ref "IC9") (pin "7") (pinfunction "SNS+_7") (pintype "power_in"))
    )
    (net (code "60") (name "Net-(IC9-SNS-)") (class "Default")
      (node (ref "C21") (pin "1") (pinfunction "1_1") (pintype "passive"))
      (node (ref "IC9") (pin "2") (pinfunction "SNS-_2") (pintype "input"))
    )
    (net (code "61") (name "Net-(IC10-IN)") (class "Default")
      (node (ref "IC10") (pin "4") (pinfunction "IN_4") (pintype "input"))
      (node (ref "R9") (pin "2") (pinfunction "2_2") (pintype "passive"))
      (node (ref "U$5") (pin "1") (pinfunction "OUTA_1") (pintype "output"))
    )
    (net (code "62") (name "Net-(IC10-OUT+)") (class "Default")
      (node (ref "IC10") (pin "8") (pinfunction "OUT+_8") (pintype "output"))
      (node (ref "J11") (pin "3") (pinfunction "3_3") (pintype "passive"))
    )
    (net (code "63") (name "Net-(IC10-OUT-)") (class "Default")
      (node (ref "IC10") (pin "1") (pinfunction "OUT-_1") (pintype "output"))
      (node (ref "J11") (pin "2") (pinfunction "2_2") (pintype "passive"))
    )
    (net (code "64") (name "Net-(IC10-SNS+)") (class "Default")
      (node (ref "C26") (pin "1") (pinfunction "1_1") (pintype "passive"))
      (node (ref "IC10") (pin "7") (pinfunction "SNS+_7") (pintype "power_in"))
    )
    (net (code "65") (name "Net-(IC10-SNS-)") (class "Default")
      (node (ref "C25") (pin "1") (pinfunction "1_1") (pintype "passive"))
      (node (ref "IC10") (pin "2") (pinfunction "SNS-_2") (pintype "input"))
    )
    (net (code "66") (name "Net-(IC11-IN+)") (class "Default")
      (node (ref "IC11") (pin "3") (pinfunction "IN+_3") (pintype "input"))
      (node (ref "J12") (pin "1") (pinfunction "1_1") (pintype "passive"))
    )
    (net (code "67") (name "Net-(IC11-IN-)") (class "Default")
      (node (ref "IC11") (pin "2") (pinfunction "IN-_2") (pintype "input"))
      (node (ref "J12") (pin "2") (pinfunction "2_2") (pintype "passive"))
    )
    (net (code "68") (name "Net-(IC11-REF)") (class "Default")
      (node (ref "IC11") (pin "1") (pinfunction "REF_1") (pintype "input"))
      (node (ref "R17") (pin "1") (pinfunction "1_1") (pintype "passive"))
    )
    (net (code "69") (name "Net-(IC12-IN+)") (class "Default")
      (node (ref "IC12") (pin "3") (pinfunction "IN+_3") (pintype "input"))
      (node (ref "J13") (pin "1") (pinfunction "1_1") (pintype "passive"))
    )
    (net (code "70") (name "Net-(IC12-IN-)") (class "Default")
      (node (ref "IC12") (pin "2") (pinfunction "IN-_2") (pintype "input"))
      (node (ref "J13") (pin "2") (pinfunction "2_2") (pintype "passive"))
    )
    (net (code "71") (name "Net-(IC12-REF)") (class "Default")
      (node (ref "IC12") (pin "1") (pinfunction "REF_1") (pintype "input"))
      (node (ref "R21") (pin "1") (pinfunction "1_1") (pintype "passive"))
    )
    (net (code "72") (name "Net-(U$1-D1)") (class "Default")
      (node (ref "R2") (pin "1") (pinfunction "1_1") (pintype "passive"))
      (node (ref "U$1") (pin "6") (pinfunction "D1_6") (pintype "output"))
    )
    (net (code "73") (name "Net-(U$1-D2)") (class "Default")
      (node (ref "R3") (pin "1") (pinfunction "1_1") (pintype "passive"))
      (node (ref "U$1") (pin "8") (pinfunction "D2_8") (pintype "output"))
    )
    (net (code "74") (name "Net-(U$1-D3)") (class "Default")
      (node (ref "R4") (pin "1") (pinfunction "1_1") (pintype "passive"))
      (node (ref "U$1") (pin "10") (pinfunction "D3_10") (pintype "output"))
    )
    (net (code "75") (name "Net-(U$1-D4)") (class "Default")
      (node (ref "R5") (pin "1") (pinfunction "1_1") (pintype "passive"))
      (node (ref "U$1") (pin "12") (pinfunction "D4_12") (pintype "output"))
    )
    (net (code "76") (name "Net-(U$1-D5)") (class "Default")
      (node (ref "R12") (pin "1") (pinfunction "1_1") (pintype "passive"))
      (node (ref "U$1") (pin "13") (pinfunction "D5_13") (pintype "output"))
    )
    (net (code "77") (name "Net-(U$1-D6)") (class "Default")
      (node (ref "R6") (pin "1") (pinfunction "1_1") (pintype "passive"))
      (node (ref "U$1") (pin "15") (pinfunction "D6_15") (pintype "output"))
    )
    (net (code "78") (name "Net-(U$1-D7)") (class "Default")
      (node (ref "R7") (pin "1") (pinfunction "1_1") (pintype "passive"))
      (node (ref "U$1") (pin "17") (pinfunction "D7_17") (pintype "output"))
    )
    (net (code "79") (name "Net-(U$1-D8)") (class "Default")
      (node (ref "R8") (pin "1") (pinfunction "1_1") (pintype "passive"))
      (node (ref "U$1") (pin "19") (pinfunction "D8_19") (pintype "output"))
    )
    (net (code "80") (name "Net-(U$2-D1)") (class "Default")
      (node (ref "R18") (pin "1") (pinfunction "1_1") (pintype "passive"))
      (node (ref "U$2") (pin "6") (pinfunction "D1_6") (pintype "output"))
    )
    (net (code "81") (name "Net-(U$2-D2)") (class "Default")
      (node (ref "R23") (pin "1") (pinfunction "1_1") (pintype "passive"))
      (node (ref "U$2") (pin "8") (pinfunction "D2_8") (pintype "output"))
    )
    (net (code "82") (name "Net-(U$2-D3)") (class "Default")
      (node (ref "R24") (pin "1") (pinfunction "1_1") (pintype "passive"))
      (node (ref "U$2") (pin "10") (pinfunction "D3_10") (pintype "output"))
    )
    (net (code "83") (name "Net-(U$2-D4)") (class "Default")
      (node (ref "R25") (pin "1") (pinfunction "1_1") (pintype "passive"))
      (node (ref "U$2") (pin "12") (pinfunction "D4_12") (pintype "output"))
    )
    (net (code "84") (name "Net-(U$2-D5)") (class "Default")
      (node (ref "R22") (pin "1") (pinfunction "1_1") (pintype "passive"))
      (node (ref "U$2") (pin "13") (pinfunction "D5_13") (pintype "output"))
    )
    (net (code "85") (name "Net-(U$2-D6)") (class "Default")
      (node (ref "R26") (pin "1") (pinfunction "1_1") (pintype "passive"))
      (node (ref "U$2") (pin "15") (pinfunction "D6_15") (pintype "output"))
    )
    (net (code "86") (name "Net-(U$2-D7)") (class "Default")
      (node (ref "R27") (pin "1") (pinfunction "1_1") (pintype "passive"))
      (node (ref "U$2") (pin "17") (pinfunction "D7_17") (pintype "output"))
    )
    (net (code "87") (name "Net-(U$2-D8)") (class "Default")
      (node (ref "R28") (pin "1") (pinfunction "1_1") (pintype "passive"))
      (node (ref "U$2") (pin "19") (pinfunction "D8_19") (pintype "output"))
    )
    (net (code "88") (name "VCC") (class "Default")
      (node (ref "C1") (pin "1") (pinfunction "1_1") (pintype "passive"))
      (node (ref "C10") (pin "1") (pinfunction "1_1") (pintype "passive"))
      (node (ref "C14") (pin "2") (pinfunction "2_2") (pintype "passive"))
      (node (ref "C15") (pin "2") (pinfunction "2_2") (pintype "passive"))
      (node (ref "C19") (pin "2") (pinfunction "2_2") (pintype "passive"))
      (node (ref "C23") (pin "2") (pinfunction "2_2") (pintype "passive"))
      (node (ref "C27") (pin "2") (pinfunction "2_2") (pintype "passive"))
      (node (ref "C28") (pin "2") (pinfunction "2_2") (pintype "passive"))
      (node (ref "C3") (pin "2") (pinfunction "2_2") (pintype "passive"))
      (node (ref "C33") (pin "2") (pinfunction "2_2") (pintype "passive"))
      (node (ref "C38") (pin "2") (pinfunction "2_2") (pintype "passive"))
      (node (ref "C43") (pin "2") (pinfunction "2_2") (pintype "passive"))
      (node (ref "C47") (pin "1") (pinfunction "1_1") (pintype "passive"))
      (node (ref "C49") (pin "1") (pinfunction "1_1") (pintype "passive"))
      (node (ref "C5") (pin "2") (pinfunction "2_2") (pintype "passive"))
      (node (ref "C52") (pin "2") (pinfunction "2_2") (pintype "passive"))
      (node (ref "C6") (pin "2") (pinfunction "2_2") (pintype "passive"))
      (node (ref "C7") (pin "2") (pinfunction "2_2") (pintype "passive"))
      (node (ref "IC1") (pin "7") (pinfunction "VCC_7") (pintype "power_in"))
      (node (ref "IC10") (pin "6") (pinfunction "VCC_6") (pintype "bidirectional"))
      (node (ref "IC11") (pin "7") (pinfunction "VCC_7") (pintype "power_in"))
      (node (ref "IC12") (pin "7") (pinfunction "VCC_7") (pintype "power_in"))
      (node (ref "IC2") (pin "6") (pinfunction "VCC_6") (pintype "bidirectional"))
      (node (ref "IC3") (pin "6") (pinfunction "VCC_6") (pintype "bidirectional"))
      (node (ref "IC4") (pin "6") (pinfunction "VCC_6") (pintype "bidirectional"))
      (node (ref "IC5") (pin "7") (pinfunction "VCC_7") (pintype "power_in"))
      (node (ref "IC6") (pin "6") (pinfunction "VCC_6") (pintype "bidirectional"))
      (node (ref "IC7") (pin "6") (pinfunction "VCC_6") (pintype "bidirectional"))
      (node (ref "IC8") (pin "6") (pinfunction "VCC_6") (pintype "bidirectional"))
      (node (ref "IC9") (pin "6") (pinfunction "VCC_6") (pintype "bidirectional"))
      (node (ref "J1") (pin "1") (pinfunction "1_1") (pintype "passive"))
      (node (ref "U$1") (pin "2") (pinfunction "VDD_2") (pintype "power_in"))
      (node (ref "U$2") (pin "2") (pinfunction "VDD_2") (pintype "power_in"))
      (node (ref "U$3") (pin "8") (pinfunction "V+_8") (pintype "power_in"))
      (node (ref "U$4") (pin "8") (pinfunction "V+_8") (pintype "power_in"))
      (node (ref "U$5") (pin "8") (pinfunction "V+_8") (pintype "power_in"))
      (node (ref "U$6") (pin "8") (pinfunction "V+_8") (pintype "power_in"))
    )
    (net (code "89") (name "VEE") (class "Default")
      (node (ref "C11") (pin "1") (pinfunction "1_1") (pintype "passive"))
      (node (ref "C12") (pin "1") (pinfunction "1_1") (pintype "passive"))
      (node (ref "C16") (pin "1") (pinfunction "1_1") (pintype "passive"))
      (node (ref "C2") (pin "1") (pinfunction "1_1") (pintype "passive"))
      (node (ref "C20") (pin "1") (pinfunction "1_1") (pintype "passive"))
      (node (ref "C24") (pin "1") (pinfunction "1_1") (pintype "passive"))
      (node (ref "C29") (pin "1") (pinfunction "1_1") (pintype "passive"))
      (node (ref "C32") (pin "1") (pinfunction "1_1") (pintype "passive"))
      (node (ref "C34") (pin "1") (pinfunction "1_1") (pintype "passive"))
      (node (ref "C37") (pin "1") (pinfunction "1_1") (pintype "passive"))
      (node (ref "C39") (pin "1") (pinfunction "1_1") (pintype "passive"))
      (node (ref "C4") (pin "1") (pinfunction "1_1") (pintype "passive"))
      (node (ref "C42") (pin "1") (pinfunction "1_1") (pintype "passive"))
      (node (ref "C44") (pin "1") (pinfunction "1_1") (pintype "passive"))
      (node (ref "C48") (pin "1") (pinfunction "1_1") (pintype "passive"))
      (node (ref "C50") (pin "1") (pinfunction "1_1") (pintype "passive"))
      (node (ref "C51") (pin "1") (pinfunction "1_1") (pintype "passive"))
      (node (ref "C8") (pin "1") (pinfunction "1_1") (pintype "passive"))
      (node (ref "IC1") (pin "4") (pinfunction "VEE_4") (pintype "power_in"))
      (node (ref "IC10") (pin "5") (pinfunction "VEE_5") (pintype "input"))
      (node (ref "IC11") (pin "4") (pinfunction "VEE_4") (pintype "power_in"))
      (node (ref "IC12") (pin "4") (pinfunction "VEE_4") (pintype "power_in"))
      (node (ref "IC2") (pin "5") (pinfunction "VEE_5") (pintype "input"))
      (node (ref "IC3") (pin "5") (pinfunction "VEE_5") (pintype "input"))
      (node (ref "IC4") (pin "5") (pinfunction "VEE_5") (pintype "input"))
      (node (ref "IC5") (pin "4") (pinfunction "VEE_4") (pintype "power_in"))
      (node (ref "IC6") (pin "5") (pinfunction "VEE_5") (pintype "input"))
      (node (ref "IC7") (pin "5") (pinfunction "VEE_5") (pintype "input"))
      (node (ref "IC8") (pin "5") (pinfunction "VEE_5") (pintype "input"))
      (node (ref "IC9") (pin "5") (pinfunction "VEE_5") (pintype "input"))
      (node (ref "J1") (pin "3") (pinfunction "3_3") (pintype "passive"))
      (node (ref "U$1") (pin "21") (pinfunction "VSS_21") (pintype "power_in"))
      (node (ref "U$2") (pin "21") (pinfunction "VSS_21") (pintype "power_in"))
      (node (ref "U$3") (pin "4") (pinfunction "V-_4") (pintype "power_in"))
      (node (ref "U$4") (pin "4") (pinfunction "V-_4") (pintype "power_in"))
      (node (ref "U$5") (pin "4") (pinfunction "V-_4") (pintype "power_in"))
      (node (ref "U$6") (pin "4") (pinfunction "V-_4") (pintype "power_in"))
    )
  )
)
